# Sheet1.net
KiCad netlist of a schematic drawn in Altium Designer
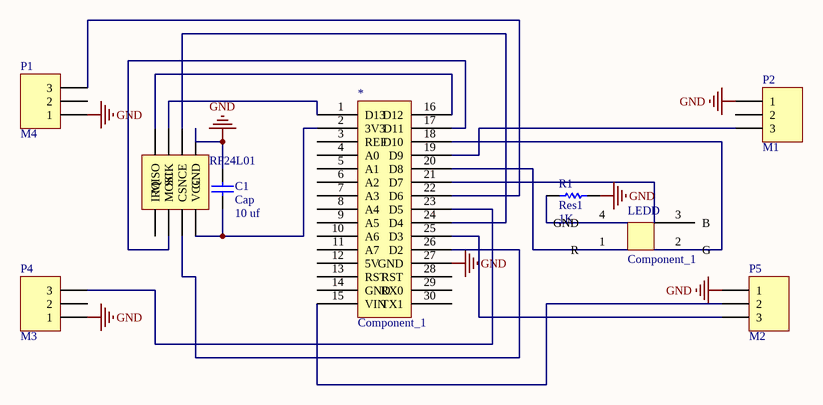
[diagram p0: Sheet1.SchDoc]

(export (version "E")
  (design (tool "Eeschema 10.0.6"))
  (components
    (comp (ref "*")
      (value "Component_1")
      (footprint "PCBComponent_1")
      (libsource (lib "Schlib2") (part "Component_1"))
    )
    (comp (ref "C1")
      (value "Cap")
      (footprint "RAD-0.1")
      (description "Capacitor")
      (fields (field (name "ALTIUM_VALUE") "10 uf") (field (name "PUBLISHER") "Altium Limited"))
      (libsource (lib "Miscellaneous Devices") (part "Cap"))
    )
    (comp (ref "LED")
      (value "Component_1")
      (footprint "LED")
      (libsource (lib "Schlib1") (part "Component_1"))
    )
    (comp (ref "P1")
      (value "M4")
      (footprint "HDR1X3")
      (description "Header, 3-Pin")
      (fields (field (name "PUBLISHER") "Altium Limited"))
      (libsource (lib "") (part "Header 3_1"))
    )
    (comp (ref "P2")
      (value "M1")
      (footprint "HDR1X3")
      (description "Header, 3-Pin")
      (fields (field (name "PUBLISHER") "Altium Limited"))
      (libsource (lib "Miscellaneous Connectors") (part "Header 3"))
    )
    (comp (ref "P4")
      (value "M3")
      (footprint "HDR1X3")
      (description "Header, 3-Pin")
      (fields (field (name "PUBLISHER") "Altium Limited"))
      (libsource (lib "") (part "Header 3_1"))
    )
    (comp (ref "P5")
      (value "M2")
      (footprint "HDR1X3")
      (description "Header, 3-Pin")
      (fields (field (name "PUBLISHER") "Altium Limited"))
      (libsource (lib "Miscellaneous Connectors") (part "Header 3"))
    )
    (comp (ref "R1")
      (value "Res1")
      (footprint "AXIAL-0.3")
      (description "Resistor")
      (fields (field (name "ALTIUM_VALUE") "1K") (field (name "PUBLISHER") "Altium Limited"))
      (libsource (lib "Miscellaneous Devices") (part "Res1"))
    )
    (comp (ref "RF24L01")
      (value "Header 4X2H")
      (footprint "HDR2X4H")
      (description "Header, 4-Pin, Dual row, Right Angle")
      (fields (field (name "PUBLISHER") "Altium Limited"))
      (libsource (lib "Miscellaneous Connectors") (part "Header 4X2H"))
    )
  )
  (nets
    (net (code "1") (name "GND") (class "Default")
      (node (ref "*") (pin "27") (pinfunction "GND_27") (pintype "passive"))
      (node (ref "C1") (pin "1") (pinfunction "1_1") (pintype "passive"))
      (node (ref "P1") (pin "1") (pinfunction "1_1") (pintype "passive"))
      (node (ref "P2") (pin "1") (pinfunction "1_1") (pintype "passive"))
      (node (ref "P4") (pin "1") (pinfunction "1_1") (pintype "passive"))
      (node (ref "P5") (pin "1") (pinfunction "1_1") (pintype "passive"))
      (node (ref "R1") (pin "2") (pinfunction "2_2") (pintype "passive"))
      (node (ref "RF24L01") (pin "1") (pinfunction "GND_1") (pintype "passive"))
    )
    (net (code "2") (name "Net-(*-3V3)") (class "Default")
      (node (ref "*") (pin "2") (pinfunction "3V3_2") (pintype "passive"))
      (node (ref "C1") (pin "2") (pinfunction "2_2") (pintype "passive"))
      (node (ref "RF24L01") (pin "2") (pinfunction "VCC_2") (pintype "passive"))
    )
    (net (code "3") (name "Net-(*-D2)") (class "Default")
      (node (ref "*") (pin "26") (pinfunction "D2_26") (pintype "passive"))
      (node (ref "RF24L01") (pin "4") (pinfunction "CSN_4") (pintype "passive"))
    )
    (net (code "4") (name "Net-(*-D3)") (class "Default")
      (node (ref "*") (pin "25") (pinfunction "D3_25") (pintype "passive"))
      (node (ref "P5") (pin "3") (pinfunction "3_3") (pintype "passive"))
    )
    (net (code "5") (name "Net-(*-D4)") (class "Default")
      (node (ref "*") (pin "24") (pinfunction "D4_24") (pintype "passive"))
      (node (ref "RF24L01") (pin "3") (pinfunction "CE_3") (pintype "passive"))
    )
    (net (code "6") (name "Net-(*-D5)") (class "Default")
      (node (ref "*") (pin "23") (pinfunction "D5_23") (pintype "passive"))
      (node (ref "P4") (pin "3") (pinfunction "3_3") (pintype "passive"))
    )
    (net (code "7") (name "Net-(*-D6)") (class "Default")
      (node (ref "*") (pin "22") (pinfunction "D6_22") (pintype "passive"))
      (node (ref "P1") (pin "3") (pinfunction "3_3") (pintype "passive"))
    )
    (net (code "8") (name "Net-(*-D7)") (class "Default")
      (node (ref "*") (pin "21") (pinfunction "D7_21") (pintype "passive"))
      (node (ref "LED") (pin "3") (pinfunction "B_3") (pintype "passive"))
    )
    (net (code "9") (name "Net-(*-D8)") (class "Default")
      (node (ref "*") (pin "20") (pinfunction "D8_20") (pintype "passive"))
      (node (ref "LED") (pin "1") (pinfunction "R_1") (pintype "passive"))
    )
    (net (code "10") (name "Net-(*-D9)") (class "Default")
      (node (ref "*") (pin "19") (pinfunction "D9_19") (pintype "passive"))
      (node (ref "P2") (pin "3") (pinfunction "3_3") (pintype "passive"))
    )
    (net (code "11") (name "Net-(*-D10)") (class "Default")
      (node (ref "*") (pin "18") (pinfunction "D10_18") (pintype "passive"))
      (node (ref "LED") (pin "2") (pinfunction "G_2") (pintype "passive"))
    )
    (net (code "12") (name "Net-(*-D11)") (class "Default")
      (node (ref "*") (pin "17") (pinfunction "D11_17") (pintype "passive"))
      (node (ref "RF24L01") (pin "6") (pinfunction "MOSI_6") (pintype "passive"))
    )
    (net (code "13") (name "Net-(*-D12)") (class "Default")
      (node (ref "*") (pin "16") (pinfunction "D12_16") (pintype "passive"))
      (node (ref "RF24L01") (pin "7") (pinfunction "MISO_7") (pintype "passive"))
    )
    (net (code "14") (name "Net-(*-D13)") (class "Default")
      (node (ref "*") (pin "1") (pinfunction "D13_1") (pintype "passive"))
      (node (ref "RF24L01") (pin "5") (pinfunction "SCK_5") (pintype "passive"))
    )
    (net (code "15") (name "Net-(*-VIN)") (class "Default")
      (node (ref "*") (pin "15") (pinfunction "VIN_15") (pintype "passive"))
      (node (ref "P5") (pin "2") (pinfunction "2_2") (pintype "passive"))
    )
    (net (code "16") (name "Net-(LEDD-GND)") (class "Default")
      (node (ref "LED") (pin "4") (pinfunction "GND_4") (pintype "passive"))
      (node (ref "R1") (pin "1") (pinfunction "1_1") (pintype "passive"))
    )
    (net (code "17") (name "unconnected-(*-5V-Pad12)") (class "Default")
      (node (ref "*") (pin "12") (pinfunction "5V_12") (pintype "passive"))
    )
    (net (code "18") (name "unconnected-(*-A0-Pad4)") (class "Default")
      (node (ref "*") (pin "4") (pinfunction "A0_4") (pintype "passive"))
    )
    (net (code "19") (name "unconnected-(*-A1-Pad5)") (class "Default")
      (node (ref "*") (pin "5") (pinfunction "A1_5") (pintype "passive"))
    )
    (net (code "20") (name "unconnected-(*-A2-Pad6)") (class "Default")
      (node (ref "*") (pin "6") (pinfunction "A2_6") (pintype "passive"))
    )
    (net (code "21") (name "unconnected-(*-A3-Pad7)") (class "Default")
      (node (ref "*") (pin "7") (pinfunction "A3_7") (pintype "passive"))
    )
    (net (code "22") (name "unconnected-(*-A4-Pad8)") (class "Default")
      (node (ref "*") (pin "8") (pinfunction "A4_8") (pintype "passive"))
    )
    (net (code "23") (name "unconnected-(*-A5-Pad9)") (class "Default")
      (node (ref "*") (pin "9") (pinfunction "A5_9") (pintype "passive"))
    )
    (net (code "24") (name "unconnected-(*-A6-Pad10)") (class "Default")
      (node (ref "*") (pin "10") (pinfunction "A6_10") (pintype "passive"))
    )
    (net (code "25") (name "unconnected-(*-A7-Pad11)") (class "Default")
      (node (ref "*") (pin "11") (pinfunction "A7_11") (pintype "passive"))
    )
    (net (code "26") (name "unconnected-(*-GND-Pad14)") (class "Default")
      (node (ref "*") (pin "14") (pinfunction "GND_14") (pintype "passive"))
    )
    (net (code "27") (name "unconnected-(*-REF-Pad3)") (class "Default")
      (node (ref "*") (pin "3") (pinfunction "REF_3") (pintype "passive"))
    )
    (net (code "28") (name "unconnected-(*-RST-Pad13)") (class "Default")
      (node (ref "*") (pin "13") (pinfunction "RST_13") (pintype "passive"))
    )
    (net (code "29") (name "unconnected-(*-RST-Pad28)") (class "Default")
      (node (ref "*") (pin "28") (pinfunction "RST_28") (pintype "passive"))
    )
    (net (code "30") (name "unconnected-(*-RX0-Pad29)") (class "Default")
      (node (ref "*") (pin "29") (pinfunction "RX0_29") (pintype "passive"))
    )
    (net (code "31") (name "unconnected-(*-TX1-Pad30)") (class "Default")
      (node (ref "*") (pin "30") (pinfunction "TX1_30") (pintype "passive"))
    )
    (net (code "32") (name "unconnected-(P1-Pad2)") (class "Default")
      (node (ref "P1") (pin "2") (pinfunction "2_2") (pintype "passive"))
    )
    (net (code "33") (name "unconnected-(P2-Pad2)") (class "Default")
      (node (ref "P2") (pin "2") (pinfunction "2_2") (pintype "passive"))
    )
    (net (code "34") (name "unconnected-(P4-Pad2)") (class "Default")
      (node (ref "P4") (pin "2") (pinfunction "2_2") (pintype "passive"))
    )
    (net (code "35") (name "unconnected-(RF24L01-IRQ-Pad8)") (class "Default")
      (node (ref "RF24L01") (pin "8") (pinfunction "IRQ_8") (pintype "passive"))
    )
  )
)
